# MODULE_1.net
KiCad netlist of a schematic drawn in Altium Designer
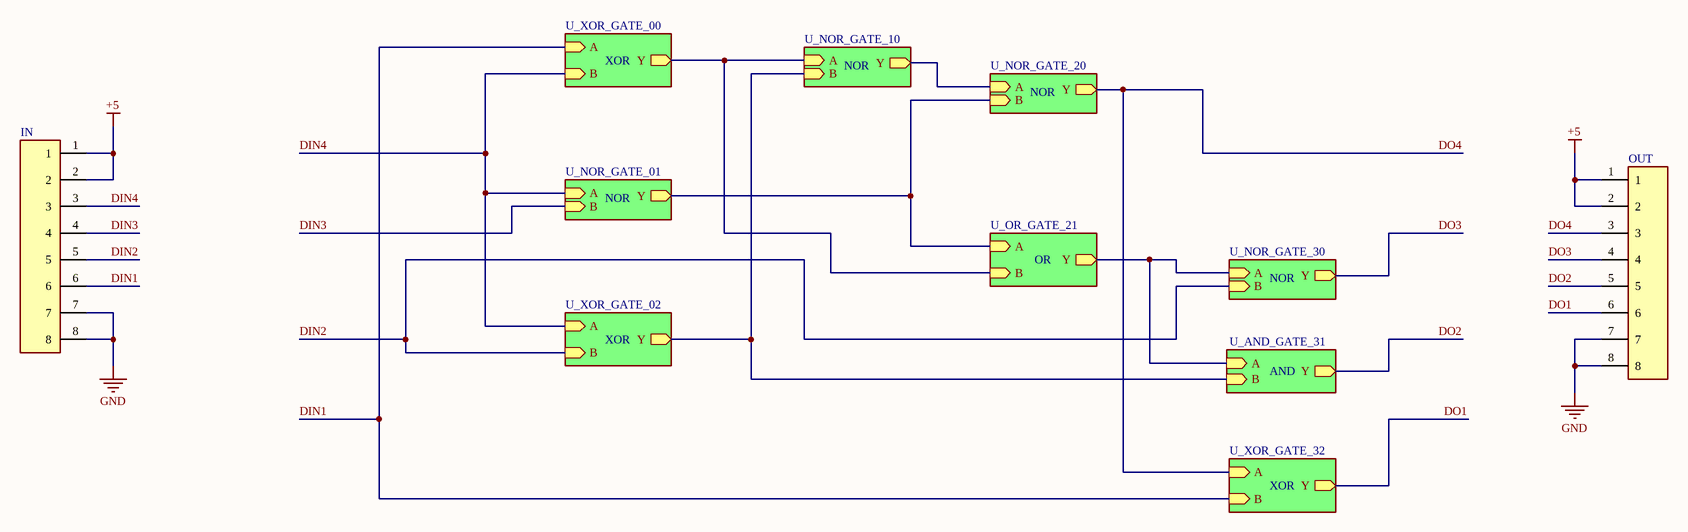
[diagram p0: MODULE_1.SchDoc]

(export (version "E")
  (design (tool "Eeschema 10.0.6"))
  (components
    (comp (ref "IN")
      (value "2.54mm_TH_1x8_pin_header")
      (footprint "2.54mm_TH_1x8_pin_header")
      (libsource (lib "") (part "2.54mm_TH_1x8_pin_header_1"))
    )
    (comp (ref "OUT")
      (value "2.54mm_TH_1x8_pin_header")
      (footprint "2.54mm_TH_1x8_pin_header")
      (libsource (lib "ARAF_PERSONAL_INTEGRATED_LIBRARY") (part "2.54mm_TH_1x8_pin_header"))
    )
  )
  (nets
    (net (code "1") (name "+5") (class "Default")
      (node (ref "IN") (pin "1") (pinfunction "1_1") (pintype "passive"))
      (node (ref "IN") (pin "2") (pinfunction "2_2") (pintype "passive"))
      (node (ref "OUT") (pin "1") (pinfunction "1_1") (pintype "passive"))
      (node (ref "OUT") (pin "2") (pinfunction "2_2") (pintype "passive"))
    )
    (net (code "2") (name "/DIN1") (class "Default")
      (node (ref "IN") (pin "6") (pinfunction "6_6") (pintype "passive"))
    )
    (net (code "3") (name "/DIN2") (class "Default")
      (node (ref "IN") (pin "5") (pinfunction "5_5") (pintype "passive"))
    )
    (net (code "4") (name "/DIN3") (class "Default")
      (node (ref "IN") (pin "4") (pinfunction "4_4") (pintype "passive"))
    )
    (net (code "5") (name "/DIN4") (class "Default")
      (node (ref "IN") (pin "3") (pinfunction "3_3") (pintype "passive"))
    )
    (net (code "6") (name "/DO1") (class "Default")
      (node (ref "OUT") (pin "6") (pinfunction "6_6") (pintype "passive"))
    )
    (net (code "7") (name "/DO2") (class "Default")
      (node (ref "OUT") (pin "5") (pinfunction "5_5") (pintype "passive"))
    )
    (net (code "8") (name "/DO3") (class "Default")
      (node (ref "OUT") (pin "4") (pinfunction "4_4") (pintype "passive"))
    )
    (net (code "9") (name "/DO4") (class "Default")
      (node (ref "OUT") (pin "3") (pinfunction "3_3") (pintype "passive"))
    )
    (net (code "15") (name "GND") (class "Default")
      (node (ref "IN") (pin "7") (pinfunction "7_7") (pintype "passive"))
      (node (ref "IN") (pin "8") (pinfunction "8_8") (pintype "passive"))
      (node (ref "OUT") (pin "7") (pinfunction "7_7") (pintype "passive"))
      (node (ref "OUT") (pin "8") (pinfunction "8_8") (pintype "passive"))
    )
  )
)
